# DS1302_SD2098.net
KiCad netlist of a schematic drawn in Altium Designer
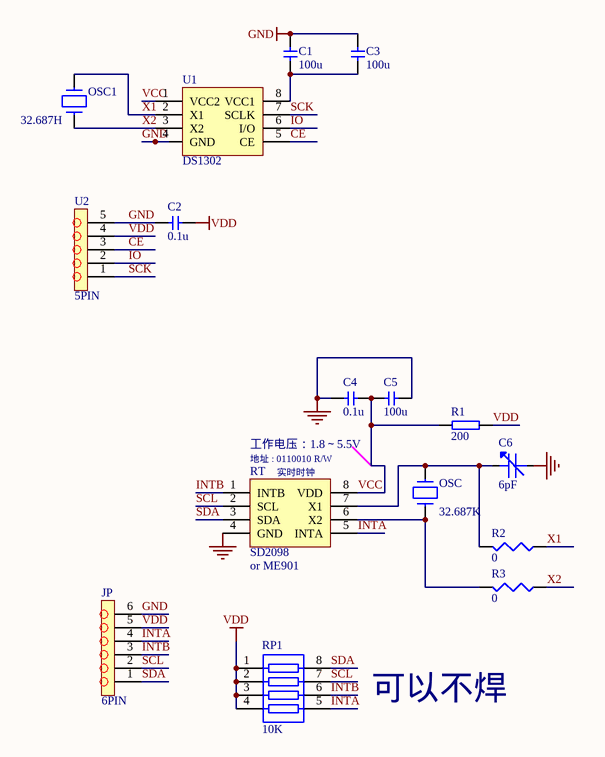
[diagram p0: DS1302_SD2098.SchDoc]

(export (version "E")
  (design (tool "Eeschema 10.0.6"))
  (components
    (comp (ref "C1") (value "100u") (footprint "RC100") (libsource (lib "Common") (part "CAPA")))
    (comp (ref "C2") (value "0.1u") (footprint "RC100") (libsource (lib "Common") (part "CAPA")))
    (comp (ref "C3") (value "100u") (footprint "RC100") (libsource (lib "Common") (part "CAPA")))
    (comp (ref "C4") (value "0.1u") (footprint "RC100") (libsource (lib "Common") (part "CAPA")))
    (comp (ref "C5") (value "100u") (footprint "RC100") (libsource (lib "Common") (part "CAPA")))
    (comp (ref "C6") (value "6pF") (footprint "RC100") (libsource (lib "Common") (part "CAPVAR")))
    (comp (ref "JP") (value "6PIN") (footprint "SIP6") (libsource (lib "Common") (part "6PIN")))
    (comp (ref "OSC") (value "32.687K") (footprint "OSC200") (libsource (lib "Common") (part "CRYSTAL")))
    (comp (ref "OSC1") (value "32.687H") (footprint "OSC100") (libsource (lib "Common") (part "CRYSTAL")))
    (comp (ref "R1") (value "200") (footprint "0805") (libsource (lib "Common") (part "RES2A")))
    (comp (ref "R2") (value "0") (footprint "0805") (libsource (lib "Common") (part "RES2B")))
    (comp (ref "R3") (value "0") (footprint "0805") (libsource (lib "Common") (part "RES2B")))
    (comp (ref "RP1") (value "10K") (footprint "RN4") (libsource (lib "Common") (part "RESPACK4")))
    (comp (ref "RT") (value "SD2098") (footprint "SOP-8_212") (libsource (lib "Common") (part "SD2098")))
    (comp (ref "U1") (value "DS1302") (footprint "SO-8-197") (libsource (lib "Common") (part "DS1302")))
    (comp (ref "U2") (value "5PIN") (footprint "SIP5") (libsource (lib "Common") (part "5PIN")))
  )
  (nets
    (net (code "1") (name "/CE") (class "Default")
      (node (ref "U1") (pin "5") (pinfunction "CE_5") (pintype "passive"))
      (node (ref "U2") (pin "3") (pintype "passive"))
    )
    (net (code "2") (name "/INTA") (class "Default")
      (node (ref "JP") (pin "4") (pintype "passive"))
      (node (ref "RP1") (pin "5") (pintype "passive"))
      (node (ref "RT") (pin "5") (pinfunction "INTA_5") (pintype "passive"))
    )
    (net (code "3") (name "/INTB") (class "Default")
      (node (ref "JP") (pin "3") (pintype "passive"))
      (node (ref "RP1") (pin "6") (pintype "passive"))
      (node (ref "RT") (pin "1") (pinfunction "INTB_1") (pintype "passive"))
    )
    (net (code "4") (name "/IO") (class "Default")
      (node (ref "U1") (pin "6") (pinfunction "I/O_6") (pintype "passive"))
      (node (ref "U2") (pin "2") (pintype "passive"))
    )
    (net (code "5") (name "/SCK") (class "Default")
      (node (ref "U1") (pin "7") (pinfunction "SCLK_7") (pintype "passive"))
      (node (ref "U2") (pin "1") (pintype "passive"))
    )
    (net (code "6") (name "/SCL") (class "Default")
      (node (ref "JP") (pin "2") (pintype "passive"))
      (node (ref "RP1") (pin "7") (pintype "passive"))
      (node (ref "RT") (pin "2") (pinfunction "SCL_2") (pintype "passive"))
    )
    (net (code "7") (name "/SDA") (class "Default")
      (node (ref "JP") (pin "1") (pintype "passive"))
      (node (ref "RP1") (pin "8") (pintype "passive"))
      (node (ref "RT") (pin "3") (pinfunction "SDA_3") (pintype "passive"))
    )
    (net (code "8") (name "/VCC") (class "Default")
      (node (ref "C4") (pin "2") (pintype "passive"))
      (node (ref "C5") (pin "1") (pintype "passive"))
      (node (ref "R1") (pin "1") (pintype "passive"))
      (node (ref "RT") (pin "8") (pinfunction "VDD_8") (pintype "passive"))
      (node (ref "U1") (pin "1") (pinfunction "VCC2_1") (pintype "passive"))
    )
    (net (code "9") (name "/X1") (class "Default")
      (node (ref "OSC1") (pin "2") (pintype "passive"))
      (node (ref "R2") (pin "1") (pintype "passive"))
      (node (ref "U1") (pin "2") (pinfunction "X1_2") (pintype "passive"))
    )
    (net (code "10") (name "/X2") (class "Default")
      (node (ref "OSC1") (pin "1") (pintype "passive"))
      (node (ref "R3") (pin "1") (pintype "passive"))
      (node (ref "U1") (pin "3") (pinfunction "X2_3") (pintype "passive"))
    )
    (net (code "11") (name "GND") (class "Default")
      (node (ref "C1") (pin "1") (pintype "passive"))
      (node (ref "C2") (pin "1") (pintype "passive"))
      (node (ref "C3") (pin "1") (pintype "passive"))
      (node (ref "C4") (pin "1") (pintype "passive"))
      (node (ref "C5") (pin "2") (pintype "passive"))
      (node (ref "C6") (pin "2") (pintype "passive"))
      (node (ref "JP") (pin "6") (pintype "passive"))
      (node (ref "RT") (pin "4") (pinfunction "GND_4") (pintype "passive"))
      (node (ref "U1") (pin "4") (pinfunction "GND_4") (pintype "passive"))
      (node (ref "U2") (pin "5") (pintype "passive"))
    )
    (net (code "12") (name "Net-(RT-X1)") (class "Default")
      (node (ref "C6") (pin "1") (pintype "passive"))
      (node (ref "OSC") (pin "2") (pintype "passive"))
      (node (ref "R2") (pin "2") (pintype "passive"))
      (node (ref "RT") (pin "7") (pinfunction "X1_7") (pintype "passive"))
    )
    (net (code "13") (name "Net-(RT-X2)") (class "Default")
      (node (ref "OSC") (pin "1") (pintype "passive"))
      (node (ref "R3") (pin "2") (pintype "passive"))
      (node (ref "RT") (pin "6") (pinfunction "X2_6") (pintype "passive"))
    )
    (net (code "14") (name "Net-(U1-VCC1)") (class "Default")
      (node (ref "C1") (pin "2") (pintype "passive"))
      (node (ref "C3") (pin "2") (pintype "passive"))
      (node (ref "U1") (pin "8") (pinfunction "VCC1_8") (pintype "passive"))
    )
    (net (code "15") (name "VDD") (class "Default")
      (node (ref "C2") (pin "2") (pintype "passive"))
      (node (ref "JP") (pin "5") (pintype "passive"))
      (node (ref "R1") (pin "2") (pintype "passive"))
      (node (ref "RP1") (pin "1") (pintype "passive"))
      (node (ref "RP1") (pin "2") (pintype "passive"))
      (node (ref "RP1") (pin "3") (pintype "passive"))
      (node (ref "RP1") (pin "4") (pintype "passive"))
      (node (ref "U2") (pin "4") (pintype "passive"))
    )
  )
)
